# Poulailler.net
KiCad netlist of a schematic drawn in EAGLE
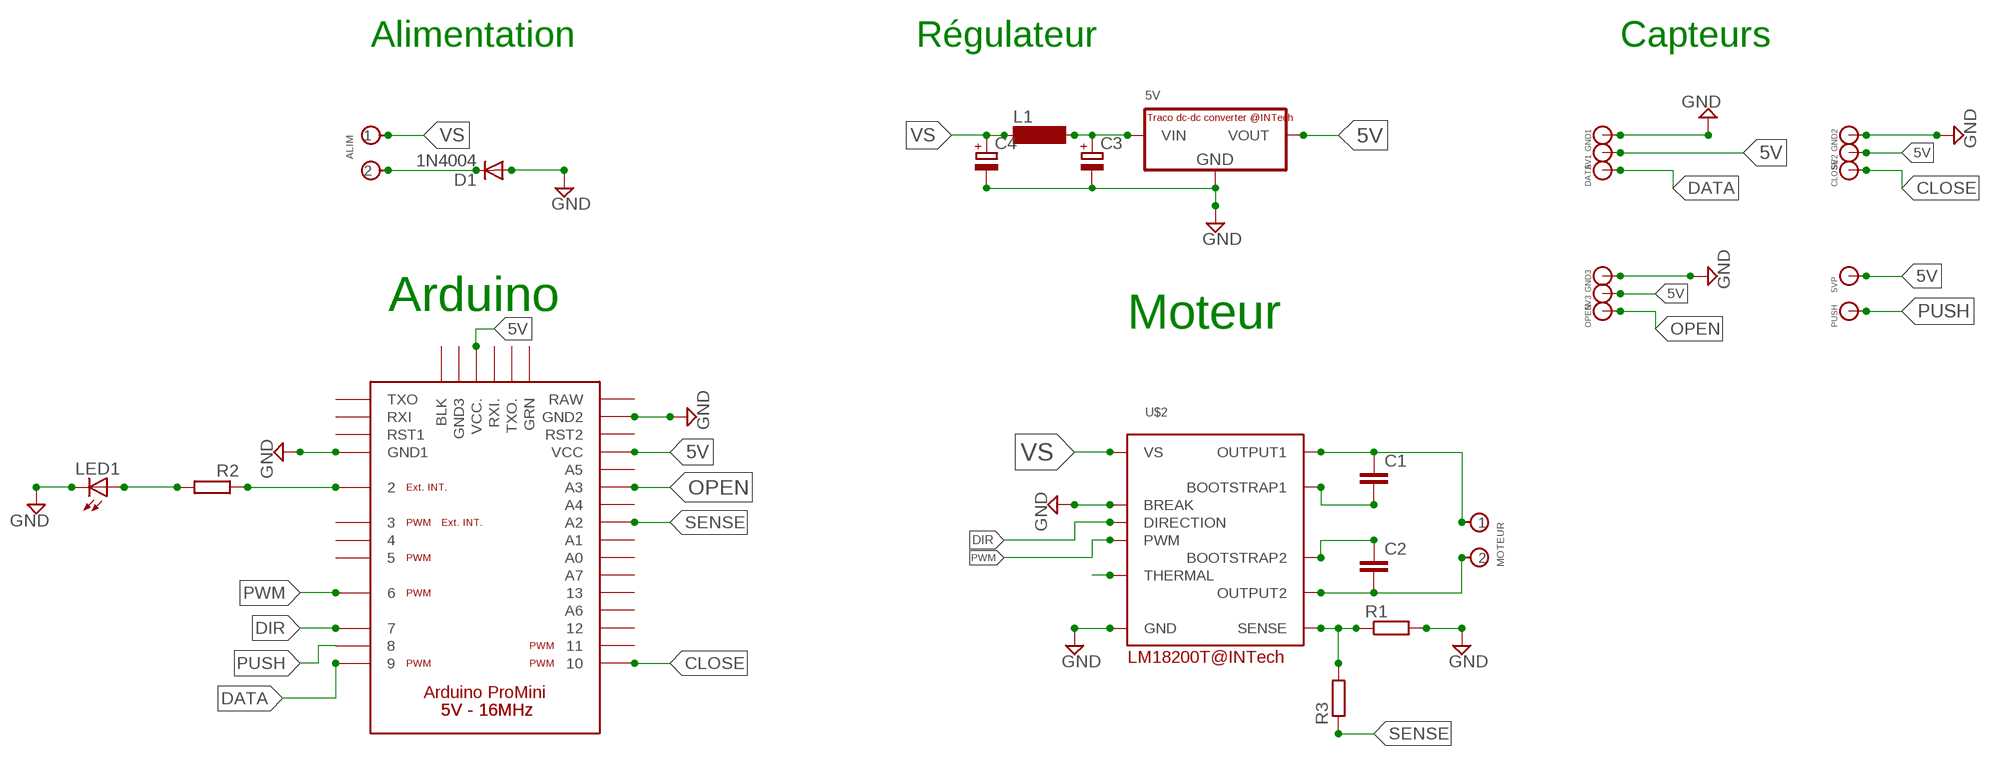
[diagram p0: schematic, sheet 1]

(export (version "E")
  (design (tool "Eeschema 10.0.6"))
  (components
    (comp (ref "5V")
      (value "R-78C-1.0_INTECH")
      (footprint "eagle-import:SIP3_INTECH")
      (libsource (lib "eagle-import") (part "R-78C-1.0_INTECH"))
    )
    (comp (ref "5V1")
      (value "SOLPAD-1_CF_INTECH")
      (footprint "eagle-import:SOLPAD-1")
      (libsource (lib "eagle-import") (part "SOLPAD-1_CF_INTECH"))
    )
    (comp (ref "5V2")
      (value "SOLPAD-1_CF_INTECH")
      (footprint "eagle-import:SOLPAD-1")
      (libsource (lib "eagle-import") (part "SOLPAD-1_CF_INTECH"))
    )
    (comp (ref "5V3")
      (value "SOLPAD-1_CF_INTECH")
      (footprint "eagle-import:SOLPAD-1")
      (libsource (lib "eagle-import") (part "SOLPAD-1_CF_INTECH"))
    )
    (comp (ref "5VP")
      (value "SOLPAD-1_CF_INTECH")
      (footprint "eagle-import:SOLPAD-1")
      (libsource (lib "eagle-import") (part "SOLPAD-1_CF_INTECH"))
    )
    (comp (ref "ALIM")
      (value "BORNIER-2")
      (footprint "eagle-import:BORNIER-2")
      (libsource (lib "eagle-import") (part "BORNIER-2"))
    )
    (comp (ref "C1")
      (value "C-EU025-025X050")
      (footprint "eagle-import:C025-025X050")
      (libsource (lib "eagle-import") (part "C-EU025-025X050"))
    )
    (comp (ref "C2")
      (value "C-EU025-025X050")
      (footprint "eagle-import:C025-025X050")
      (libsource (lib "eagle-import") (part "C-EU025-025X050"))
    )
    (comp (ref "C3")
      (value "CPOL-EUE2,5-6E")
      (footprint "eagle-import:E2,5-6E")
      (libsource (lib "eagle-import") (part "CPOL-EUE2,5-6E"))
    )
    (comp (ref "C4")
      (value "CPOL-EUE2,5-6E")
      (footprint "eagle-import:E2,5-6E")
      (libsource (lib "eagle-import") (part "CPOL-EUE2,5-6E"))
    )
    (comp (ref "CLOSE")
      (value "SOLPAD-1_CF_INTECH")
      (footprint "eagle-import:SOLPAD-1")
      (libsource (lib "eagle-import") (part "SOLPAD-1_CF_INTECH"))
    )
    (comp (ref "D1")
      (value "1N4004")
      (footprint "eagle-import:DO41-10")
      (libsource (lib "eagle-import") (part "1N4004"))
    )
    (comp (ref "DATA")
      (value "SOLPAD-1_CF_INTECH")
      (footprint "eagle-import:SOLPAD-1")
      (libsource (lib "eagle-import") (part "SOLPAD-1_CF_INTECH"))
    )
    (comp (ref "GND1")
      (value "SOLPAD-1_CF_INTECH")
      (footprint "eagle-import:SOLPAD-1")
      (libsource (lib "eagle-import") (part "SOLPAD-1_CF_INTECH"))
    )
    (comp (ref "GND2")
      (value "SOLPAD-1_CF_INTECH")
      (footprint "eagle-import:SOLPAD-1")
      (libsource (lib "eagle-import") (part "SOLPAD-1_CF_INTECH"))
    )
    (comp (ref "GND3")
      (value "SOLPAD-1_CF_INTECH")
      (footprint "eagle-import:SOLPAD-1")
      (libsource (lib "eagle-import") (part "SOLPAD-1_CF_INTECH"))
    )
    (comp (ref "L1")
      (value "SD12-1000")
      (footprint "eagle-import:SD12_1000")
      (libsource (lib "eagle-import") (part "SD12-1000"))
    )
    (comp (ref "LED1")
      (value "LED3MM")
      (footprint "eagle-import:LED3MM")
      (libsource (lib "eagle-import") (part "LED3MM"))
    )
    (comp (ref "MOTEUR")
      (value "BORNIER-2")
      (footprint "eagle-import:BORNIER-2")
      (libsource (lib "eagle-import") (part "BORNIER-2"))
    )
    (comp (ref "OPEN")
      (value "SOLPAD-1_CF_INTECH")
      (footprint "eagle-import:SOLPAD-1")
      (libsource (lib "eagle-import") (part "SOLPAD-1_CF_INTECH"))
    )
    (comp (ref "PUSH")
      (value "SOLPAD-1_CF_INTECH")
      (footprint "eagle-import:SOLPAD-1")
      (libsource (lib "eagle-import") (part "SOLPAD-1_CF_INTECH"))
    )
    (comp (ref "R1")
      (value "R-EU_0204/5")
      (footprint "eagle-import:0204_5")
      (libsource (lib "eagle-import") (part "R-EU_0204/5"))
    )
    (comp (ref "R2")
      (value "R-EU_0204/5")
      (footprint "eagle-import:0204_5")
      (libsource (lib "eagle-import") (part "R-EU_0204/5"))
    )
    (comp (ref "R3")
      (value "R-EU_0204/5")
      (footprint "eagle-import:0204_5")
      (libsource (lib "eagle-import") (part "R-EU_0204/5"))
    )
    (comp (ref "U$1")
      (value "ARDUINO_PRO_MINI")
      (footprint "eagle-import:ARDUINO_PRO_MINI")
      (libsource (lib "eagle-import") (part "ARDUINO_PRO_MINI"))
    )
    (comp (ref "U$2")
      (value "LM18200T_CF_INTECH")
      (footprint "eagle-import:LM18200T_CF_INTECH")
      (libsource (lib "eagle-import") (part "LM18200T_CF_INTECH"))
    )
  )
  (nets
    (net (code "1") (name "5V") (class "Default")
      (node (ref "5V") (pin "VOUT") (pinfunction "VOUT_VOUT") (pintype "passive"))
      (node (ref "5V1") (pin "DATA") (pinfunction "DATA_DATA") (pintype "bidirectional"))
      (node (ref "5V2") (pin "DATA") (pinfunction "DATA_DATA") (pintype "bidirectional"))
      (node (ref "5V3") (pin "DATA") (pinfunction "DATA_DATA") (pintype "bidirectional"))
      (node (ref "5VP") (pin "DATA") (pinfunction "DATA_DATA") (pintype "bidirectional"))
      (node (ref "U$1") (pin "VCC1") (pinfunction "VCC_VCC1") (pintype "bidirectional"))
      (node (ref "U$1") (pin "VCC2") (pinfunction "VCC._VCC2") (pintype "bidirectional"))
    )
    (net (code "2") (name "CLOSE") (class "Default")
      (node (ref "CLOSE") (pin "DATA") (pinfunction "DATA_DATA") (pintype "bidirectional"))
      (node (ref "U$1") (pin "10") (pinfunction "10_10") (pintype "bidirectional"))
    )
    (net (code "3") (name "DATA") (class "Default")
      (node (ref "DATA") (pin "DATA") (pinfunction "DATA_DATA") (pintype "bidirectional"))
      (node (ref "U$1") (pin "9") (pinfunction "9_9") (pintype "bidirectional"))
    )
    (net (code "4") (name "DIR") (class "Default")
      (node (ref "U$1") (pin "7") (pinfunction "7_7") (pintype "bidirectional"))
      (node (ref "U$2") (pin "3") (pinfunction "DIRECTION_3") (pintype "input"))
    )
    (net (code "5") (name "GND") (class "Default")
      (node (ref "5V") (pin "GND") (pinfunction "GND_GND") (pintype "passive"))
      (node (ref "C3") (pin "-") (pinfunction "-_-") (pintype "passive"))
      (node (ref "C4") (pin "-") (pinfunction "-_-") (pintype "passive"))
      (node (ref "D1") (pin "A") (pinfunction "A_A") (pintype "passive"))
      (node (ref "GND1") (pin "DATA") (pinfunction "DATA_DATA") (pintype "bidirectional"))
      (node (ref "GND2") (pin "DATA") (pinfunction "DATA_DATA") (pintype "bidirectional"))
      (node (ref "GND3") (pin "DATA") (pinfunction "DATA_DATA") (pintype "bidirectional"))
      (node (ref "LED1") (pin "K") (pinfunction "C_K") (pintype "passive"))
      (node (ref "R1") (pin "2") (pinfunction "2_2") (pintype "passive"))
      (node (ref "U$1") (pin "GND1") (pinfunction "GND1_GND1") (pintype "bidirectional"))
      (node (ref "U$1") (pin "GND2") (pinfunction "GND2_GND2") (pintype "bidirectional"))
      (node (ref "U$2") (pin "4") (pinfunction "BREAK_4") (pintype "input"))
      (node (ref "U$2") (pin "7") (pinfunction "GND_7") (pintype "power_in"))
    )
    (net (code "6") (name "Net-(5V-PadVIN)") (class "Default")
      (node (ref "5V") (pin "VIN") (pinfunction "VIN_VIN") (pintype "passive"))
      (node (ref "C3") (pin "+") (pinfunction "+_+") (pintype "passive"))
      (node (ref "L1") (pin "2") (pinfunction "2_2") (pintype "passive"))
    )
    (net (code "7") (name "Net-(ALIM-Pad2)") (class "Default")
      (node (ref "ALIM") (pin "2") (pinfunction "2_2") (pintype "bidirectional"))
      (node (ref "D1") (pin "C") (pinfunction "C_C") (pintype "passive"))
    )
    (net (code "8") (name "Net-(LED1-PadA)") (class "Default")
      (node (ref "LED1") (pin "A") (pinfunction "A_A") (pintype "passive"))
      (node (ref "R2") (pin "2") (pinfunction "2_2") (pintype "passive"))
    )
    (net (code "9") (name "Net-(R2-Pad1)") (class "Default")
      (node (ref "R2") (pin "1") (pinfunction "1_1") (pintype "passive"))
      (node (ref "U$1") (pin "2") (pinfunction "2_2") (pintype "bidirectional"))
    )
    (net (code "10") (name "Net-(U$2-BOOTSTRAP1)") (class "Default")
      (node (ref "C1") (pin "2") (pinfunction "2_2") (pintype "passive"))
      (node (ref "U$2") (pin "1") (pinfunction "BOOTSTRAP1_1") (pintype "input"))
    )
    (net (code "11") (name "Net-(U$2-BOOTSTRAP2)") (class "Default")
      (node (ref "C2") (pin "1") (pinfunction "1_1") (pintype "passive"))
      (node (ref "U$2") (pin "11") (pinfunction "BOOTSTRAP2_11") (pintype "input"))
    )
    (net (code "12") (name "Net-(U$2-OUTPUT1)") (class "Default")
      (node (ref "C1") (pin "1") (pinfunction "1_1") (pintype "passive"))
      (node (ref "MOTEUR") (pin "1") (pinfunction "1_1") (pintype "bidirectional"))
      (node (ref "U$2") (pin "2") (pinfunction "OUTPUT1_2") (pintype "output"))
    )
    (net (code "13") (name "Net-(U$2-OUTPUT2)") (class "Default")
      (node (ref "C2") (pin "2") (pinfunction "2_2") (pintype "passive"))
      (node (ref "MOTEUR") (pin "2") (pinfunction "2_2") (pintype "bidirectional"))
      (node (ref "U$2") (pin "10") (pinfunction "OUTPUT2_10") (pintype "output"))
    )
    (net (code "14") (name "Net-(U$2-SENSE)") (class "Default")
      (node (ref "R1") (pin "1") (pinfunction "1_1") (pintype "passive"))
      (node (ref "R3") (pin "2") (pinfunction "2_2") (pintype "passive"))
      (node (ref "U$2") (pin "8") (pinfunction "SENSE_8") (pintype "output"))
    )
    (net (code "15") (name "OPEN") (class "Default")
      (node (ref "OPEN") (pin "DATA") (pinfunction "DATA_DATA") (pintype "bidirectional"))
      (node (ref "U$1") (pin "A3") (pinfunction "A3_A3") (pintype "bidirectional"))
    )
    (net (code "16") (name "PUSH") (class "Default")
      (node (ref "PUSH") (pin "DATA") (pinfunction "DATA_DATA") (pintype "bidirectional"))
      (node (ref "U$1") (pin "8") (pinfunction "8_8") (pintype "bidirectional"))
    )
    (net (code "17") (name "PWM") (class "Default")
      (node (ref "U$1") (pin "6") (pinfunction "6_6") (pintype "bidirectional"))
      (node (ref "U$2") (pin "5") (pinfunction "PWM_5") (pintype "input"))
    )
    (net (code "18") (name "SENSE") (class "Default")
      (node (ref "R3") (pin "1") (pinfunction "1_1") (pintype "passive"))
      (node (ref "U$1") (pin "A2") (pinfunction "A2_A2") (pintype "bidirectional"))
    )
    (net (code "19") (name "VS") (class "Default")
      (node (ref "ALIM") (pin "1") (pinfunction "1_1") (pintype "bidirectional"))
      (node (ref "C4") (pin "+") (pinfunction "+_+") (pintype "passive"))
      (node (ref "L1") (pin "1") (pinfunction "1_1") (pintype "passive"))
      (node (ref "U$2") (pin "6") (pinfunction "VS_6") (pintype "power_in"))
    )
    (net (code "20") (name "unconnected-(U$1-Pad3)") (class "Default")
      (node (ref "U$1") (pin "3") (pinfunction "3_3") (pintype "bidirectional"))
    )
    (net (code "21") (name "unconnected-(U$1-Pad4)") (class "Default")
      (node (ref "U$1") (pin "4") (pinfunction "4_4") (pintype "bidirectional"))
    )
    (net (code "22") (name "unconnected-(U$1-Pad5)") (class "Default")
      (node (ref "U$1") (pin "5") (pinfunction "5_5") (pintype "bidirectional"))
    )
    (net (code "23") (name "unconnected-(U$1-Pad11)") (class "Default")
      (node (ref "U$1") (pin "11") (pinfunction "11_11") (pintype "bidirectional"))
    )
    (net (code "24") (name "unconnected-(U$1-Pad12)") (class "Default")
      (node (ref "U$1") (pin "12") (pinfunction "12_12") (pintype "bidirectional"))
    )
    (net (code "25") (name "unconnected-(U$1-Pad13)") (class "Default")
      (node (ref "U$1") (pin "13") (pinfunction "13_13") (pintype "bidirectional"))
    )
    (net (code "26") (name "unconnected-(U$1-PadA0)") (class "Default")
      (node (ref "U$1") (pin "A0") (pinfunction "A0_A0") (pintype "bidirectional"))
    )
    (net (code "27") (name "unconnected-(U$1-PadA1)") (class "Default")
      (node (ref "U$1") (pin "A1") (pinfunction "A1_A1") (pintype "bidirectional"))
    )
    (net (code "28") (name "unconnected-(U$1-PadA4)") (class "Default")
      (node (ref "U$1") (pin "A4") (pinfunction "A4_A4") (pintype "bidirectional"))
    )
    (net (code "29") (name "unconnected-(U$1-PadA5)") (class "Default")
      (node (ref "U$1") (pin "A5") (pinfunction "A5_A5") (pintype "bidirectional"))
    )
    (net (code "30") (name "unconnected-(U$1-PadA6)") (class "Default")
      (node (ref "U$1") (pin "A6") (pinfunction "A6_A6") (pintype "bidirectional"))
    )
    (net (code "31") (name "unconnected-(U$1-PadA7)") (class "Default")
      (node (ref "U$1") (pin "A7") (pinfunction "A7_A7") (pintype "bidirectional"))
    )
    (net (code "32") (name "unconnected-(U$1-PadBLK)") (class "Default")
      (node (ref "U$1") (pin "BLK") (pinfunction "BLK_BLK") (pintype "bidirectional"))
    )
    (net (code "33") (name "unconnected-(U$1-PadGND3)") (class "Default")
      (node (ref "U$1") (pin "GND3") (pinfunction "GND3_GND3") (pintype "bidirectional"))
    )
    (net (code "34") (name "unconnected-(U$1-PadGRN)") (class "Default")
      (node (ref "U$1") (pin "GRN") (pinfunction "GRN_GRN") (pintype "bidirectional"))
    )
    (net (code "35") (name "unconnected-(U$1-PadRAW)") (class "Default")
      (node (ref "U$1") (pin "RAW") (pinfunction "RAW_RAW") (pintype "bidirectional"))
    )
    (net (code "36") (name "unconnected-(U$1-PadRST1)") (class "Default")
      (node (ref "U$1") (pin "RST1") (pinfunction "RST1_RST1") (pintype "bidirectional"))
    )
    (net (code "37") (name "unconnected-(U$1-PadRST2)") (class "Default")
      (node (ref "U$1") (pin "RST2") (pinfunction "RST2_RST2") (pintype "bidirectional"))
    )
    (net (code "38") (name "unconnected-(U$1-RXI-PadRXI1)") (class "Default")
      (node (ref "U$1") (pin "RXI1") (pinfunction "RXI_RXI1") (pintype "bidirectional"))
    )
    (net (code "39") (name "unconnected-(U$1-RXI.-PadRXI2)") (class "Default")
      (node (ref "U$1") (pin "RXI2") (pinfunction "RXI._RXI2") (pintype "bidirectional"))
    )
    (net (code "40") (name "unconnected-(U$1-TXO-PadTXO1)") (class "Default")
      (node (ref "U$1") (pin "TXO1") (pinfunction "TXO_TXO1") (pintype "bidirectional"))
    )
    (net (code "41") (name "unconnected-(U$1-TXO.-PadTXO2)") (class "Default")
      (node (ref "U$1") (pin "TXO2") (pinfunction "TXO._TXO2") (pintype "bidirectional"))
    )
    (net (code "42") (name "unconnected-(U$2-THERMAL-Pad9)") (class "Default")
      (node (ref "U$2") (pin "9") (pinfunction "THERMAL_9") (pintype "output"))
    )
  )
)
